# SampleAndHold.net
KiCad netlist of a schematic drawn in Altium Designer
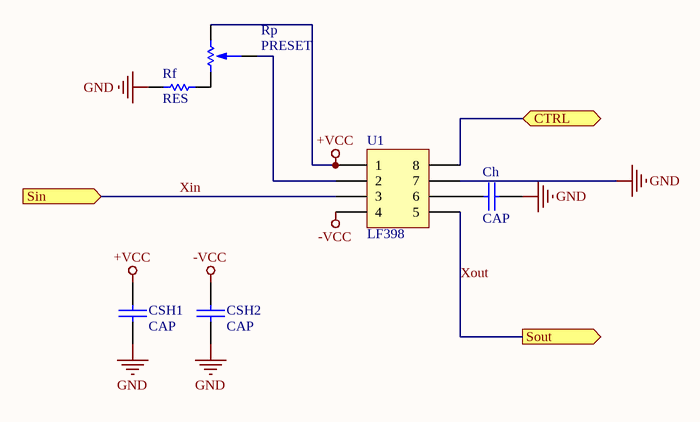
[diagram p0: SampleAndHold.SchDoc]

(export (version "E")
  (design (tool "Eeschema 10.0.6"))
  (components
    (comp (ref "Ch") (value "CAP") (footprint "CAP200") (libsource (lib "Schematics") (part "CAP")))
    (comp (ref "CSH1") (value "CAP") (footprint "CAP200") (libsource (lib "Schematics") (part "CAP")))
    (comp (ref "CSH2") (value "CAP") (footprint "CAP200") (libsource (lib "Schematics") (part "CAP")))
    (comp (ref "Rf") (value "RES") (footprint "RES400") (libsource (lib "Schematics") (part "RES")))
    (comp (ref "Rp") (value "PRESET") (footprint "PRESET V") (libsource (lib "Schematics") (part "PRESET")))
    (comp (ref "U1") (value "LF398") (footprint "DIP8") (libsource (lib "Schematics") (part "IC_DIP8")))
  )
  (nets
    (net (code "1") (name "+VCC") (class "Default")
      (node (ref "CSH1") (pin "1") (pinfunction "1_1") (pintype "passive"))
      (node (ref "Rp") (pin "1") (pinfunction "1_1") (pintype "passive"))
      (node (ref "U1") (pin "1") (pinfunction "1_1") (pintype "passive"))
    )
    (net (code "2") (name "-VCC") (class "Default")
      (node (ref "CSH2") (pin "1") (pinfunction "1_1") (pintype "passive"))
      (node (ref "U1") (pin "4") (pinfunction "4_4") (pintype "passive"))
    )
    (net (code "3") (name "/CTRL") (class "Default")
      (node (ref "U1") (pin "8") (pinfunction "8_8") (pintype "passive"))
    )
    (net (code "4") (name "/Xin") (class "Default")
      (node (ref "U1") (pin "3") (pinfunction "3_3") (pintype "passive"))
    )
    (net (code "5") (name "/Xout") (class "Default")
      (node (ref "U1") (pin "5") (pinfunction "5_5") (pintype "passive"))
    )
    (net (code "6") (name "GND") (class "Default")
      (node (ref "CSH1") (pin "2") (pinfunction "2_2") (pintype "passive"))
      (node (ref "CSH2") (pin "2") (pinfunction "2_2") (pintype "passive"))
      (node (ref "Ch") (pin "2") (pinfunction "2_2") (pintype "passive"))
      (node (ref "Rf") (pin "1") (pinfunction "1_1") (pintype "passive"))
      (node (ref "U1") (pin "7") (pinfunction "7_7") (pintype "passive"))
    )
    (net (code "7") (name "Net-(Ch-Pad1)") (class "Default")
      (node (ref "Ch") (pin "1") (pinfunction "1_1") (pintype "passive"))
      (node (ref "U1") (pin "6") (pinfunction "6_6") (pintype "passive"))
    )
    (net (code "8") (name "Net-(Rf-Pad2)") (class "Default")
      (node (ref "Rf") (pin "2") (pinfunction "2_2") (pintype "passive"))
      (node (ref "Rp") (pin "3") (pinfunction "3_3") (pintype "passive"))
    )
    (net (code "9") (name "Net-(Rp-Pad2)") (class "Default")
      (node (ref "Rp") (pin "2") (pinfunction "2_2") (pintype "passive"))
      (node (ref "U1") (pin "2") (pinfunction "2_2") (pintype "passive"))
    )
  )
)
